# 23121179.net
KiCad netlist of a schematic drawn in EasyEDA Pro
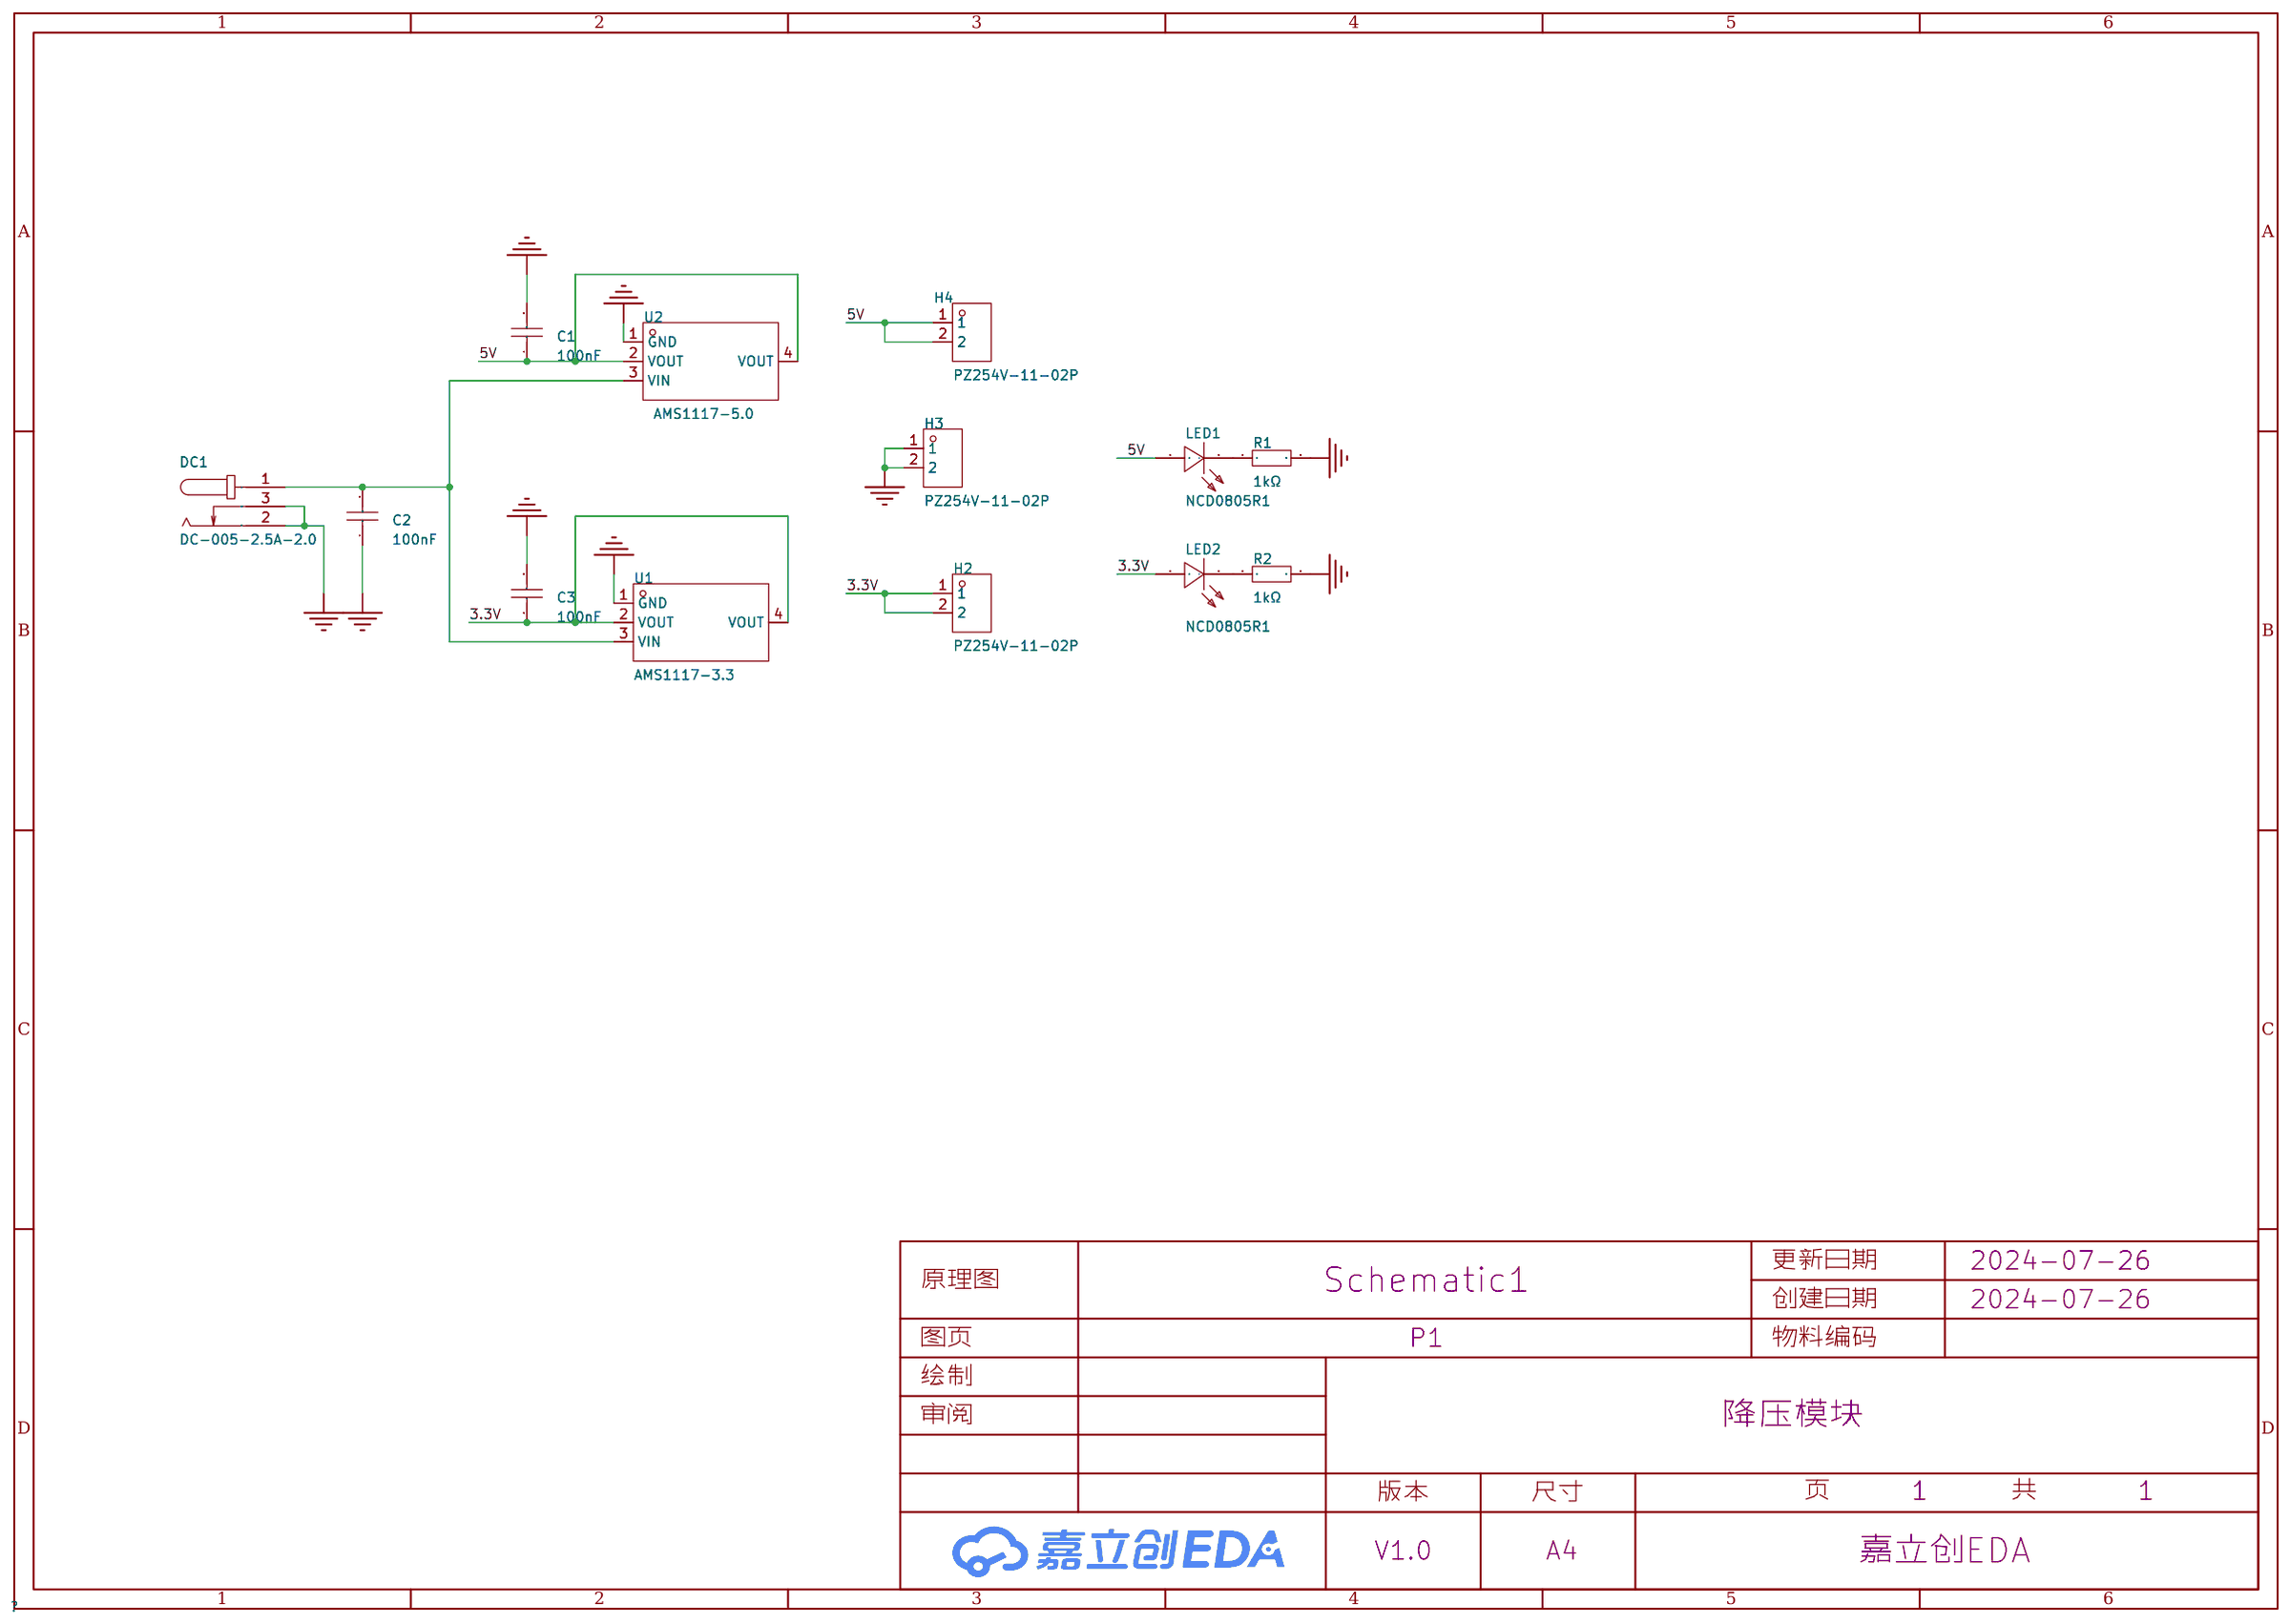
[diagram p0: schematic sheet]

(export (version "E")
  (design (tool "Eeschema 10.0.6"))
  (components
    (comp (ref "C1")
      (value "100nF")
      (footprint "easyedapro:C0805")
      (description "容值:100nF;精度:±10%;额定电压:50V;材质(温度系数):X7R;")
      (fields
        (field (name "Manufacturer Part") "CC0805KRX7R9BB104")
        (field (name "Manufacturer") "YAGEO(国巨)")
      )
      (libsource (lib "easyedapro") (part "CC0805KRX7R9BB104"))
    )
    (comp (ref "C2")
      (value "100nF")
      (footprint "easyedapro:C0805")
      (description "容值:100nF;精度:±10%;额定电压:50V;材质(温度系数):X7R;")
      (fields
        (field (name "Manufacturer Part") "CC0805KRX7R9BB104")
        (field (name "Manufacturer") "YAGEO(国巨)")
      )
      (libsource (lib "easyedapro") (part "CC0805KRX7R9BB104"))
    )
    (comp (ref "C3")
      (value "100nF")
      (footprint "easyedapro:C0805")
      (description "容值:100nF;精度:±10%;额定电压:50V;材质(温度系数):X7R;")
      (fields
        (field (name "Manufacturer Part") "CC0805KRX7R9BB104")
        (field (name "Manufacturer") "YAGEO(国巨)")
      )
      (libsource (lib "easyedapro") (part "CC0805KRX7R9BB104"))
    )
    (comp (ref "DC1")
      (value "DC-005-2.5A-2.0")
      (footprint "easyedapro:CONN-TH_DC-005-2.5A-2.0")
      (fields (field (name "Manufacturer") "XKB Connection(中国星坤)"))
      (libsource (lib "easyedapro") (part "DC-005-2.5A-2.0"))
    )
    (comp (ref "H2")
      (value "PZ254V-11-02P")
      (footprint "easyedapro:HDR-TH_2P-P2.54-V-M")
      (fields (field (name "Manufacturer") "XFCN(兴飞)"))
      (libsource (lib "easyedapro") (part "PZ254V-11-02P"))
    )
    (comp (ref "H3")
      (value "PZ254V-11-02P")
      (footprint "easyedapro:HDR-TH_2P-P2.54-V-M")
      (fields (field (name "Manufacturer") "XFCN(兴飞)"))
      (libsource (lib "easyedapro") (part "PZ254V-11-02P"))
    )
    (comp (ref "H4")
      (value "PZ254V-11-02P")
      (footprint "easyedapro:HDR-TH_2P-P2.54-V-M")
      (fields (field (name "Manufacturer") "XFCN(兴飞)"))
      (libsource (lib "easyedapro") (part "PZ254V-11-02P"))
    )
    (comp (ref "LED1")
      (value "NCD0805R1")
      (footprint "easyedapro:LED0805-R-RD")
      (fields (field (name "Manufacturer") "国星光电"))
      (libsource (lib "easyedapro") (part "FC-2012HRK-620D"))
    )
    (comp (ref "LED2")
      (value "NCD0805R1")
      (footprint "easyedapro:LED0805-R-RD")
      (fields (field (name "Manufacturer") "国星光电"))
      (libsource (lib "easyedapro") (part "FC-2012HRK-620D"))
    )
    (comp (ref "R1")
      (value "1kΩ")
      (footprint "easyedapro:R0805")
      (description "电阻类型:厚膜电阻;阻值:1kΩ;精度:±1%;功率:125mW;最大工作电压:150V;温度系数:±100ppm/°C;")
      (fields
        (field (name "Manufacturer Part") "0805W8F1001T5E")
        (field (name "Manufacturer") "UNI-ROYAL(厚声)")
      )
      (libsource (lib "easyedapro") (part "0805W8F1001T5E"))
    )
    (comp (ref "R2")
      (value "1kΩ")
      (footprint "easyedapro:R0805")
      (description "电阻类型:厚膜电阻;阻值:1kΩ;精度:±1%;功率:125mW;最大工作电压:150V;温度系数:±100ppm/°C;")
      (fields
        (field (name "Manufacturer Part") "0805W8F1001T5E")
        (field (name "Manufacturer") "UNI-ROYAL(厚声)")
      )
      (libsource (lib "easyedapro") (part "0805W8F1001T5E"))
    )
    (comp (ref "U1")
      (value "AMS1117-3.3")
      (footprint "easyedapro:SOT-223-3_L6.5-W3.4-P2.30-LS7.0-BR")
      (description "输出类型:固定;最大输入电压:-;输出电压:3.3V;最大输出电流:1A;电源纹波抑制比(PSRR):72dB@(120Hz);输出极性:正极;")
      (fields (field (name "Manufacturer") "AMS"))
      (libsource (lib "easyedapro") (part "AMS1117-3.3"))
    )
    (comp (ref "U2")
      (value "AMS1117-5.0")
      (footprint "easyedapro:SOT-223_L6.5-W3.5-P2.30-LS7.0-BR")
      (description "输出类型:固定;最大输入电压:12V;输出电压:5V;最大输出电流:1A;电源纹波抑制比(PSRR):68dB@(120Hz);输出极性:正极;")
      (fields (field (name "Manufacturer") "AMS"))
      (libsource (lib "easyedapro") (part "AMS1117-5.0"))
    )
  )
  (nets
    (net (code "1") (name "/3.3V") (class "Default")
      (node (ref "C3") (pin "1") (pinfunction "1_1") (pintype "input"))
      (node (ref "H2") (pin "1") (pinfunction "1_1") (pintype "unspecified"))
      (node (ref "H2") (pin "2") (pinfunction "2_2") (pintype "unspecified"))
      (node (ref "LED2") (pin "1") (pinfunction "+_1") (pintype "unspecified"))
      (node (ref "U1") (pin "2") (pinfunction "VOUT_2") (pintype "unspecified"))
      (node (ref "U1") (pin "4") (pinfunction "VOUT_4") (pintype "unspecified"))
    )
    (net (code "2") (name "/5V") (class "Default")
      (node (ref "C1") (pin "1") (pinfunction "1_1") (pintype "input"))
      (node (ref "H4") (pin "1") (pinfunction "1_1") (pintype "unspecified"))
      (node (ref "H4") (pin "2") (pinfunction "2_2") (pintype "unspecified"))
      (node (ref "LED1") (pin "1") (pinfunction "+_1") (pintype "unspecified"))
      (node (ref "U2") (pin "2") (pinfunction "VOUT_2") (pintype "unspecified"))
      (node (ref "U2") (pin "4") (pinfunction "VOUT_4") (pintype "unspecified"))
    )
    (net (code "3") (name "GND") (class "Default")
      (node (ref "C1") (pin "2") (pinfunction "2_2") (pintype "input"))
      (node (ref "C2") (pin "1") (pinfunction "1_1") (pintype "input"))
      (node (ref "C3") (pin "2") (pinfunction "2_2") (pintype "input"))
      (node (ref "DC1") (pin "2") (pinfunction "2_2") (pintype "unspecified"))
      (node (ref "DC1") (pin "3") (pinfunction "3_3") (pintype "unspecified"))
      (node (ref "H3") (pin "1") (pinfunction "1_1") (pintype "unspecified"))
      (node (ref "H3") (pin "2") (pinfunction "2_2") (pintype "unspecified"))
      (node (ref "R1") (pin "2") (pinfunction "2_2") (pintype "input"))
      (node (ref "R2") (pin "2") (pinfunction "2_2") (pintype "input"))
      (node (ref "U1") (pin "1") (pinfunction "GND_1") (pintype "unspecified"))
      (node (ref "U2") (pin "1") (pinfunction "GND_1") (pintype "unspecified"))
    )
    (net (code "4") (name "Net-(LED1--)") (class "Default")
      (node (ref "LED1") (pin "2") (pinfunction "-_2") (pintype "unspecified"))
      (node (ref "R1") (pin "1") (pinfunction "1_1") (pintype "input"))
    )
    (net (code "5") (name "Net-(LED2--)") (class "Default")
      (node (ref "LED2") (pin "2") (pinfunction "-_2") (pintype "unspecified"))
      (node (ref "R2") (pin "1") (pinfunction "1_1") (pintype "input"))
    )
    (net (code "6") (name "Net-(U1-VIN)") (class "Default")
      (node (ref "C2") (pin "2") (pinfunction "2_2") (pintype "input"))
      (node (ref "DC1") (pin "1") (pinfunction "1_1") (pintype "unspecified"))
      (node (ref "U1") (pin "3") (pinfunction "VIN_3") (pintype "unspecified"))
      (node (ref "U2") (pin "3") (pinfunction "VIN_3") (pintype "unspecified"))
    )
  )
)
